# BUTTON.net
KiCad netlist of a schematic drawn in Altium Designer
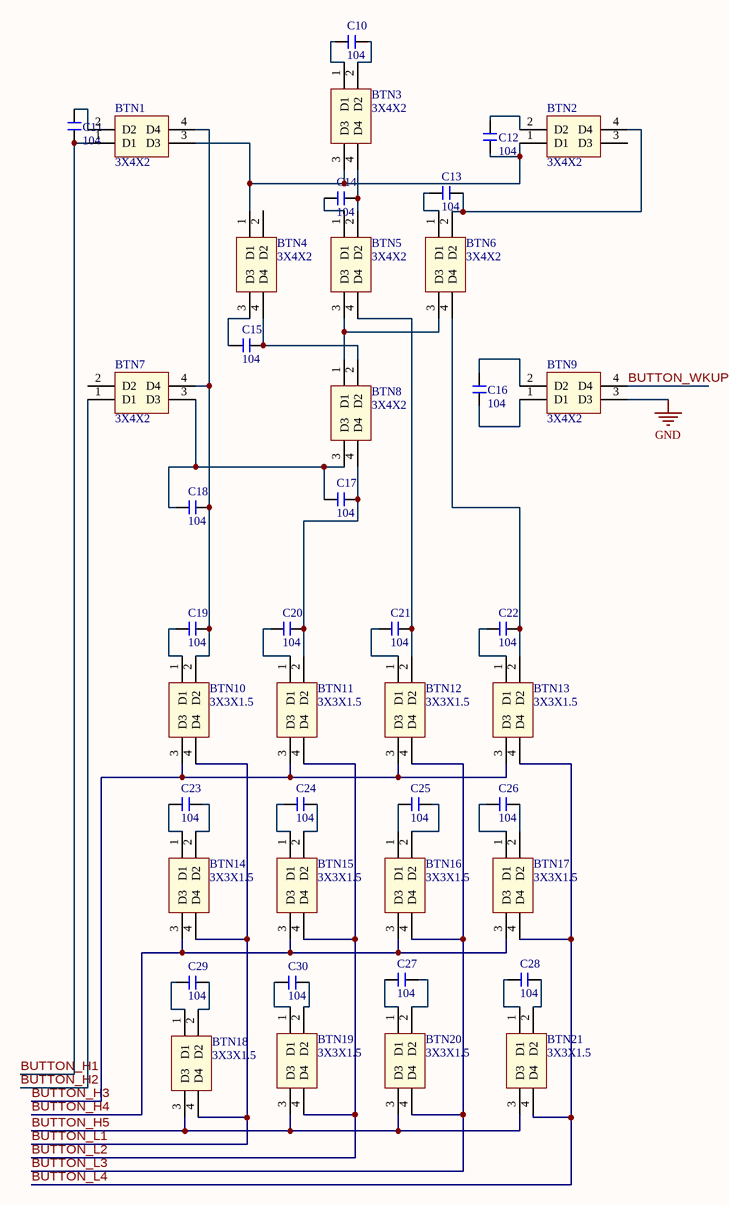
[diagram p0: BUTTON.SchDoc]

(export (version "E")
  (design (tool "Eeschema 10.0.6"))
  (components
    (comp (ref "BTN1") (value "3X4X2") (footprint "3X4X2按钮") (libsource (lib "") (part "3X4X2_1")))
    (comp (ref "BTN2") (value "3X4X2") (footprint "3X4X2按钮") (libsource (lib "") (part "3X4X2_1")))
    (comp (ref "BTN3") (value "3X4X2") (footprint "3X4X2按钮") (libsource (lib "STM32_Phone") (part "3X4X2")))
    (comp (ref "BTN4") (value "3X4X2") (footprint "3X4X2按钮") (libsource (lib "STM32_Phone") (part "3X4X2")))
    (comp (ref "BTN5") (value "3X4X2") (footprint "3X4X2按钮") (libsource (lib "STM32_Phone") (part "3X4X2")))
    (comp (ref "BTN6") (value "3X4X2") (footprint "3X4X2按钮") (libsource (lib "STM32_Phone") (part "3X4X2")))
    (comp (ref "BTN7") (value "3X4X2") (footprint "3X4X2按钮") (libsource (lib "") (part "3X4X2_1")))
    (comp (ref "BTN8") (value "3X4X2") (footprint "3X4X2按钮") (libsource (lib "STM32_Phone") (part "3X4X2")))
    (comp (ref "BTN9") (value "3X4X2") (footprint "3X4X2按钮") (libsource (lib "") (part "3X4X2_1")))
    (comp (ref "BTN10")
      (value "3X3X1.5")
      (footprint "3X3X1.5")
      (libsource (lib "STM32_Phone") (part "3X3X1.5"))
    )
    (comp (ref "BTN11")
      (value "3X3X1.5")
      (footprint "3X3X1.5")
      (libsource (lib "STM32_Phone") (part "3X3X1.5"))
    )
    (comp (ref "BTN12")
      (value "3X3X1.5")
      (footprint "3X3X1.5")
      (libsource (lib "STM32_Phone") (part "3X3X1.5"))
    )
    (comp (ref "BTN13")
      (value "3X3X1.5")
      (footprint "3X3X1.5")
      (libsource (lib "STM32_Phone") (part "3X3X1.5"))
    )
    (comp (ref "BTN14")
      (value "3X3X1.5")
      (footprint "3X3X1.5")
      (libsource (lib "STM32_Phone") (part "3X3X1.5"))
    )
    (comp (ref "BTN15")
      (value "3X3X1.5")
      (footprint "3X3X1.5")
      (libsource (lib "STM32_Phone") (part "3X3X1.5"))
    )
    (comp (ref "BTN16")
      (value "3X3X1.5")
      (footprint "3X3X1.5")
      (libsource (lib "STM32_Phone") (part "3X3X1.5"))
    )
    (comp (ref "BTN17")
      (value "3X3X1.5")
      (footprint "3X3X1.5")
      (libsource (lib "STM32_Phone") (part "3X3X1.5"))
    )
    (comp (ref "BTN18")
      (value "3X3X1.5")
      (footprint "3X3X1.5")
      (libsource (lib "STM32_Phone") (part "3X3X1.5"))
    )
    (comp (ref "BTN19")
      (value "3X3X1.5")
      (footprint "3X3X1.5")
      (libsource (lib "STM32_Phone") (part "3X3X1.5"))
    )
    (comp (ref "BTN20")
      (value "3X3X1.5")
      (footprint "3X3X1.5")
      (libsource (lib "STM32_Phone") (part "3X3X1.5"))
    )
    (comp (ref "BTN21")
      (value "3X3X1.5")
      (footprint "3X3X1.5")
      (libsource (lib "STM32_Phone") (part "3X3X1.5"))
    )
    (comp (ref "C10")
      (value "104")
      (footprint "C 0805_L")
      (description "无极性贴片电容")
      (fields (field (name "版权归属") "源创客"))
      (libsource (lib "STM32_Phone_1") (part "C"))
    )
    (comp (ref "C11")
      (value "104")
      (footprint "C 0805_L")
      (description "无极性贴片电容")
      (fields (field (name "版权归属") "源创客"))
      (libsource (lib "STM32_Phone_1") (part "C"))
    )
    (comp (ref "C12")
      (value "104")
      (footprint "C 0805_L")
      (description "无极性贴片电容")
      (fields (field (name "版权归属") "源创客"))
      (libsource (lib "STM32_Phone_1") (part "C"))
    )
    (comp (ref "C13")
      (value "104")
      (footprint "C 0805_L")
      (description "无极性贴片电容")
      (fields (field (name "版权归属") "源创客"))
      (libsource (lib "STM32_Phone_1") (part "C"))
    )
    (comp (ref "C14")
      (value "104")
      (footprint "C 0805_L")
      (description "无极性贴片电容")
      (fields (field (name "版权归属") "源创客"))
      (libsource (lib "STM32_Phone_1") (part "C"))
    )
    (comp (ref "C15")
      (value "104")
      (footprint "C 0805_L")
      (description "无极性贴片电容")
      (fields (field (name "版权归属") "源创客"))
      (libsource (lib "STM32_Phone_1") (part "C"))
    )
    (comp (ref "C16")
      (value "104")
      (footprint "C 0805_L")
      (description "无极性贴片电容")
      (fields (field (name "版权归属") "源创客"))
      (libsource (lib "STM32_Phone_1") (part "C"))
    )
    (comp (ref "C17")
      (value "104")
      (footprint "C 0805_L")
      (description "无极性贴片电容")
      (fields (field (name "版权归属") "源创客"))
      (libsource (lib "STM32_Phone_1") (part "C"))
    )
    (comp (ref "C18")
      (value "104")
      (footprint "C 0805_L")
      (description "无极性贴片电容")
      (fields (field (name "版权归属") "源创客"))
      (libsource (lib "STM32_Phone_1") (part "C"))
    )
    (comp (ref "C19")
      (value "104")
      (footprint "C 0805_L")
      (description "无极性贴片电容")
      (fields (field (name "版权归属") "源创客"))
      (libsource (lib "STM32_Phone_1") (part "C"))
    )
    (comp (ref "C20")
      (value "104")
      (footprint "C 0805_L")
      (description "无极性贴片电容")
      (fields (field (name "版权归属") "源创客"))
      (libsource (lib "STM32_Phone_1") (part "C"))
    )
    (comp (ref "C21")
      (value "104")
      (footprint "C 0805_L")
      (description "无极性贴片电容")
      (fields (field (name "版权归属") "源创客"))
      (libsource (lib "STM32_Phone_1") (part "C"))
    )
    (comp (ref "C22")
      (value "104")
      (footprint "C 0805_L")
      (description "无极性贴片电容")
      (fields (field (name "版权归属") "源创客"))
      (libsource (lib "STM32_Phone_1") (part "C"))
    )
    (comp (ref "C23")
      (value "104")
      (footprint "C 0805_L")
      (description "无极性贴片电容")
      (fields (field (name "版权归属") "源创客"))
      (libsource (lib "STM32_Phone_1") (part "C"))
    )
    (comp (ref "C24")
      (value "104")
      (footprint "C 0805_L")
      (description "无极性贴片电容")
      (fields (field (name "版权归属") "源创客"))
      (libsource (lib "STM32_Phone_1") (part "C"))
    )
    (comp (ref "C25")
      (value "104")
      (footprint "C 0805_L")
      (description "无极性贴片电容")
      (fields (field (name "版权归属") "源创客"))
      (libsource (lib "STM32_Phone_1") (part "C"))
    )
    (comp (ref "C26")
      (value "104")
      (footprint "C 0805_L")
      (description "无极性贴片电容")
      (fields (field (name "版权归属") "源创客"))
      (libsource (lib "STM32_Phone_1") (part "C"))
    )
    (comp (ref "C27")
      (value "104")
      (footprint "C 0805_L")
      (description "无极性贴片电容")
      (fields (field (name "版权归属") "源创客"))
      (libsource (lib "STM32_Phone_1") (part "C"))
    )
    (comp (ref "C28")
      (value "104")
      (footprint "C 0805_L")
      (description "无极性贴片电容")
      (fields (field (name "版权归属") "源创客"))
      (libsource (lib "STM32_Phone_1") (part "C"))
    )
    (comp (ref "C29")
      (value "104")
      (footprint "C 0805_L")
      (description "无极性贴片电容")
      (fields (field (name "版权归属") "源创客"))
      (libsource (lib "STM32_Phone_1") (part "C"))
    )
    (comp (ref "C30")
      (value "104")
      (footprint "C 0805_L")
      (description "无极性贴片电容")
      (fields (field (name "版权归属") "源创客"))
      (libsource (lib "STM32_Phone_1") (part "C"))
    )
  )
  (nets
    (net (code "1") (name "/BUTTON_H1") (class "Default")
      (node (ref "BTN1") (pin "1") (pinfunction "D1_1") (pintype "passive"))
      (node (ref "C11") (pin "1") (pinfunction "1_1") (pintype "passive"))
    )
    (net (code "2") (name "/BUTTON_H2") (class "Default")
      (node (ref "BTN7") (pin "1") (pinfunction "D1_1") (pintype "passive"))
    )
    (net (code "3") (name "/BUTTON_H3") (class "Default")
      (node (ref "BTN10") (pin "3") (pinfunction "D3_3") (pintype "passive"))
      (node (ref "BTN11") (pin "3") (pinfunction "D3_3") (pintype "passive"))
      (node (ref "BTN12") (pin "3") (pinfunction "D3_3") (pintype "passive"))
      (node (ref "BTN13") (pin "3") (pinfunction "D3_3") (pintype "passive"))
    )
    (net (code "4") (name "/BUTTON_H4") (class "Default")
      (node (ref "BTN14") (pin "3") (pinfunction "D3_3") (pintype "passive"))
      (node (ref "BTN15") (pin "3") (pinfunction "D3_3") (pintype "passive"))
      (node (ref "BTN16") (pin "3") (pinfunction "D3_3") (pintype "passive"))
      (node (ref "BTN17") (pin "3") (pinfunction "D3_3") (pintype "passive"))
    )
    (net (code "5") (name "/BUTTON_H5") (class "Default")
      (node (ref "BTN18") (pin "3") (pinfunction "D3_3") (pintype "passive"))
      (node (ref "BTN19") (pin "3") (pinfunction "D3_3") (pintype "passive"))
      (node (ref "BTN20") (pin "3") (pinfunction "D3_3") (pintype "passive"))
      (node (ref "BTN21") (pin "3") (pinfunction "D3_3") (pintype "passive"))
    )
    (net (code "6") (name "/BUTTON_L1") (class "Default")
      (node (ref "BTN10") (pin "4") (pinfunction "D4_4") (pintype "passive"))
      (node (ref "BTN14") (pin "4") (pinfunction "D4_4") (pintype "passive"))
      (node (ref "BTN18") (pin "4") (pinfunction "D4_4") (pintype "passive"))
    )
    (net (code "7") (name "/BUTTON_L2") (class "Default")
      (node (ref "BTN11") (pin "4") (pinfunction "D4_4") (pintype "passive"))
      (node (ref "BTN15") (pin "4") (pinfunction "D4_4") (pintype "passive"))
      (node (ref "BTN19") (pin "4") (pinfunction "D4_4") (pintype "passive"))
    )
    (net (code "8") (name "/BUTTON_L3") (class "Default")
      (node (ref "BTN12") (pin "4") (pinfunction "D4_4") (pintype "passive"))
      (node (ref "BTN16") (pin "4") (pinfunction "D4_4") (pintype "passive"))
      (node (ref "BTN20") (pin "4") (pinfunction "D4_4") (pintype "passive"))
    )
    (net (code "9") (name "/BUTTON_L4") (class "Default")
      (node (ref "BTN13") (pin "4") (pinfunction "D4_4") (pintype "passive"))
      (node (ref "BTN17") (pin "4") (pinfunction "D4_4") (pintype "passive"))
      (node (ref "BTN21") (pin "4") (pinfunction "D4_4") (pintype "passive"))
    )
    (net (code "10") (name "/BUTTON_WKUP") (class "Default")
      (node (ref "BTN9") (pin "4") (pinfunction "D4_4") (pintype "passive"))
    )
    (net (code "11") (name "GND") (class "Default")
      (node (ref "BTN9") (pin "3") (pinfunction "D3_3") (pintype "passive"))
    )
    (net (code "12") (name "Net-(BTN1-D2)") (class "Default")
      (node (ref "BTN1") (pin "2") (pinfunction "D2_2") (pintype "passive"))
      (node (ref "C11") (pin "2") (pinfunction "2_2") (pintype "passive"))
    )
    (net (code "13") (name "Net-(BTN1-D3)") (class "Default")
      (node (ref "BTN1") (pin "3") (pinfunction "D3_3") (pintype "passive"))
      (node (ref "BTN2") (pin "1") (pinfunction "D1_1") (pintype "passive"))
      (node (ref "BTN3") (pin "3") (pinfunction "D3_3") (pintype "passive"))
      (node (ref "BTN4") (pin "1") (pinfunction "D1_1") (pintype "passive"))
      (node (ref "C12") (pin "1") (pinfunction "1_1") (pintype "passive"))
    )
    (net (code "14") (name "Net-(BTN1-D4)") (class "Default")
      (node (ref "BTN1") (pin "4") (pinfunction "D4_4") (pintype "passive"))
      (node (ref "BTN10") (pin "2") (pinfunction "D2_2") (pintype "passive"))
      (node (ref "BTN7") (pin "4") (pinfunction "D4_4") (pintype "passive"))
      (node (ref "C18") (pin "1") (pinfunction "1_1") (pintype "passive"))
      (node (ref "C19") (pin "1") (pinfunction "1_1") (pintype "passive"))
    )
    (net (code "15") (name "Net-(BTN2-D2)") (class "Default")
      (node (ref "BTN2") (pin "2") (pinfunction "D2_2") (pintype "passive"))
      (node (ref "C12") (pin "2") (pinfunction "2_2") (pintype "passive"))
    )
    (net (code "16") (name "Net-(BTN2-D4)") (class "Default")
      (node (ref "BTN2") (pin "4") (pinfunction "D4_4") (pintype "passive"))
      (node (ref "BTN6") (pin "2") (pinfunction "D2_2") (pintype "passive"))
      (node (ref "C13") (pin "2") (pinfunction "2_2") (pintype "passive"))
    )
    (net (code "17") (name "Net-(BTN3-D1)") (class "Default")
      (node (ref "BTN3") (pin "1") (pinfunction "D1_1") (pintype "passive"))
      (node (ref "C10") (pin "1") (pinfunction "1_1") (pintype "passive"))
    )
    (net (code "18") (name "Net-(BTN3-D2)") (class "Default")
      (node (ref "BTN3") (pin "2") (pinfunction "D2_2") (pintype "passive"))
      (node (ref "C10") (pin "2") (pinfunction "2_2") (pintype "passive"))
    )
    (net (code "19") (name "Net-(BTN3-D4)") (class "Default")
      (node (ref "BTN3") (pin "4") (pinfunction "D4_4") (pintype "passive"))
      (node (ref "BTN5") (pin "2") (pinfunction "D2_2") (pintype "passive"))
      (node (ref "C14") (pin "2") (pinfunction "2_2") (pintype "passive"))
    )
    (net (code "20") (name "Net-(BTN4-D3)") (class "Default")
      (node (ref "BTN4") (pin "3") (pinfunction "D3_3") (pintype "passive"))
      (node (ref "C15") (pin "1") (pinfunction "1_1") (pintype "passive"))
    )
    (net (code "21") (name "Net-(BTN4-D4)") (class "Default")
      (node (ref "BTN4") (pin "4") (pinfunction "D4_4") (pintype "passive"))
      (node (ref "BTN8") (pin "2") (pinfunction "D2_2") (pintype "passive"))
      (node (ref "C15") (pin "2") (pinfunction "2_2") (pintype "passive"))
    )
    (net (code "22") (name "Net-(BTN5-D1)") (class "Default")
      (node (ref "BTN5") (pin "1") (pinfunction "D1_1") (pintype "passive"))
      (node (ref "C14") (pin "1") (pinfunction "1_1") (pintype "passive"))
    )
    (net (code "23") (name "Net-(BTN5-D3)") (class "Default")
      (node (ref "BTN5") (pin "3") (pinfunction "D3_3") (pintype "passive"))
      (node (ref "BTN6") (pin "3") (pinfunction "D3_3") (pintype "passive"))
      (node (ref "BTN8") (pin "1") (pinfunction "D1_1") (pintype "passive"))
    )
    (net (code "24") (name "Net-(BTN6-D1)") (class "Default")
      (node (ref "BTN6") (pin "1") (pinfunction "D1_1") (pintype "passive"))
      (node (ref "C13") (pin "1") (pinfunction "1_1") (pintype "passive"))
    )
    (net (code "25") (name "Net-(BTN7-D3)") (class "Default")
      (node (ref "BTN7") (pin "3") (pinfunction "D3_3") (pintype "passive"))
      (node (ref "BTN8") (pin "3") (pinfunction "D3_3") (pintype "passive"))
      (node (ref "C17") (pin "1") (pinfunction "1_1") (pintype "passive"))
      (node (ref "C18") (pin "2") (pinfunction "2_2") (pintype "passive"))
    )
    (net (code "26") (name "Net-(BTN9-D1)") (class "Default")
      (node (ref "BTN9") (pin "1") (pinfunction "D1_1") (pintype "passive"))
      (node (ref "C16") (pin "1") (pinfunction "1_1") (pintype "passive"))
    )
    (net (code "27") (name "Net-(BTN9-D2)") (class "Default")
      (node (ref "BTN9") (pin "2") (pinfunction "D2_2") (pintype "passive"))
      (node (ref "C16") (pin "2") (pinfunction "2_2") (pintype "passive"))
    )
    (net (code "28") (name "Net-(BTN10-D1)") (class "Default")
      (node (ref "BTN10") (pin "1") (pinfunction "D1_1") (pintype "passive"))
      (node (ref "C19") (pin "2") (pinfunction "2_2") (pintype "passive"))
    )
    (net (code "29") (name "Net-(BTN11-D1)") (class "Default")
      (node (ref "BTN11") (pin "1") (pinfunction "D1_1") (pintype "passive"))
      (node (ref "C20") (pin "2") (pinfunction "2_2") (pintype "passive"))
    )
    (net (code "30") (name "Net-(BTN11-D2)") (class "Default")
      (node (ref "BTN11") (pin "2") (pinfunction "D2_2") (pintype "passive"))
      (node (ref "BTN8") (pin "4") (pinfunction "D4_4") (pintype "passive"))
      (node (ref "C17") (pin "2") (pinfunction "2_2") (pintype "passive"))
      (node (ref "C20") (pin "1") (pinfunction "1_1") (pintype "passive"))
    )
    (net (code "31") (name "Net-(BTN12-D1)") (class "Default")
      (node (ref "BTN12") (pin "1") (pinfunction "D1_1") (pintype "passive"))
      (node (ref "C21") (pin "2") (pinfunction "2_2") (pintype "passive"))
    )
    (net (code "32") (name "Net-(BTN12-D2)") (class "Default")
      (node (ref "BTN12") (pin "2") (pinfunction "D2_2") (pintype "passive"))
      (node (ref "BTN5") (pin "4") (pinfunction "D4_4") (pintype "passive"))
      (node (ref "C21") (pin "1") (pinfunction "1_1") (pintype "passive"))
    )
    (net (code "33") (name "Net-(BTN13-D1)") (class "Default")
      (node (ref "BTN13") (pin "1") (pinfunction "D1_1") (pintype "passive"))
      (node (ref "C22") (pin "2") (pinfunction "2_2") (pintype "passive"))
    )
    (net (code "34") (name "Net-(BTN13-D2)") (class "Default")
      (node (ref "BTN13") (pin "2") (pinfunction "D2_2") (pintype "passive"))
      (node (ref "BTN6") (pin "4") (pinfunction "D4_4") (pintype "passive"))
      (node (ref "C22") (pin "1") (pinfunction "1_1") (pintype "passive"))
    )
    (net (code "35") (name "Net-(BTN14-D1)") (class "Default")
      (node (ref "BTN14") (pin "1") (pinfunction "D1_1") (pintype "passive"))
      (node (ref "C23") (pin "2") (pinfunction "2_2") (pintype "passive"))
    )
    (net (code "36") (name "Net-(BTN14-D2)") (class "Default")
      (node (ref "BTN14") (pin "2") (pinfunction "D2_2") (pintype "passive"))
      (node (ref "C23") (pin "1") (pinfunction "1_1") (pintype "passive"))
    )
    (net (code "37") (name "Net-(BTN15-D1)") (class "Default")
      (node (ref "BTN15") (pin "1") (pinfunction "D1_1") (pintype "passive"))
      (node (ref "C24") (pin "2") (pinfunction "2_2") (pintype "passive"))
    )
    (net (code "38") (name "Net-(BTN15-D2)") (class "Default")
      (node (ref "BTN15") (pin "2") (pinfunction "D2_2") (pintype "passive"))
      (node (ref "C24") (pin "1") (pinfunction "1_1") (pintype "passive"))
    )
    (net (code "39") (name "Net-(BTN16-D1)") (class "Default")
      (node (ref "BTN16") (pin "1") (pinfunction "D1_1") (pintype "passive"))
      (node (ref "C25") (pin "1") (pinfunction "1_1") (pintype "passive"))
    )
    (net (code "40") (name "Net-(BTN16-D2)") (class "Default")
      (node (ref "BTN16") (pin "2") (pinfunction "D2_2") (pintype "passive"))
      (node (ref "C25") (pin "2") (pinfunction "2_2") (pintype "passive"))
    )
    (net (code "41") (name "Net-(BTN17-D1)") (class "Default")
      (node (ref "BTN17") (pin "1") (pinfunction "D1_1") (pintype "passive"))
      (node (ref "C26") (pin "2") (pinfunction "2_2") (pintype "passive"))
    )
    (net (code "42") (name "Net-(BTN17-D2)") (class "Default")
      (node (ref "BTN17") (pin "2") (pinfunction "D2_2") (pintype "passive"))
      (node (ref "C26") (pin "1") (pinfunction "1_1") (pintype "passive"))
    )
    (net (code "43") (name "Net-(BTN18-D1)") (class "Default")
      (node (ref "BTN18") (pin "1") (pinfunction "D1_1") (pintype "passive"))
      (node (ref "C29") (pin "2") (pinfunction "2_2") (pintype "passive"))
    )
    (net (code "44") (name "Net-(BTN18-D2)") (class "Default")
      (node (ref "BTN18") (pin "2") (pinfunction "D2_2") (pintype "passive"))
      (node (ref "C29") (pin "1") (pinfunction "1_1") (pintype "passive"))
    )
    (net (code "45") (name "Net-(BTN19-D1)") (class "Default")
      (node (ref "BTN19") (pin "1") (pinfunction "D1_1") (pintype "passive"))
      (node (ref "C30") (pin "2") (pinfunction "2_2") (pintype "passive"))
    )
    (net (code "46") (name "Net-(BTN19-D2)") (class "Default")
      (node (ref "BTN19") (pin "2") (pinfunction "D2_2") (pintype "passive"))
      (node (ref "C30") (pin "1") (pinfunction "1_1") (pintype "passive"))
    )
    (net (code "47") (name "Net-(BTN20-D1)") (class "Default")
      (node (ref "BTN20") (pin "1") (pinfunction "D1_1") (pintype "passive"))
      (node (ref "C27") (pin "2") (pinfunction "2_2") (pintype "passive"))
    )
    (net (code "48") (name "Net-(BTN20-D2)") (class "Default")
      (node (ref "BTN20") (pin "2") (pinfunction "D2_2") (pintype "passive"))
      (node (ref "C27") (pin "1") (pinfunction "1_1") (pintype "passive"))
    )
    (net (code "49") (name "Net-(BTN21-D1)") (class "Default")
      (node (ref "BTN21") (pin "1") (pinfunction "D1_1") (pintype "passive"))
      (node (ref "C28") (pin "2") (pinfunction "2_2") (pintype "passive"))
    )
    (net (code "50") (name "Net-(BTN21-D2)") (class "Default")
      (node (ref "BTN21") (pin "2") (pinfunction "D2_2") (pintype "passive"))
      (node (ref "C28") (pin "1") (pinfunction "1_1") (pintype "passive"))
    )
    (net (code "51") (name "unconnected-(BTN2-D3-Pad3)") (class "Default")
      (node (ref "BTN2") (pin "3") (pinfunction "D3_3") (pintype "passive"))
    )
    (net (code "52") (name "unconnected-(BTN4-D2-Pad2)") (class "Default")
      (node (ref "BTN4") (pin "2") (pinfunction "D2_2") (pintype "passive"))
    )
    (net (code "53") (name "unconnected-(BTN7-D2-Pad2)") (class "Default")
      (node (ref "BTN7") (pin "2") (pinfunction "D2_2") (pintype "passive"))
    )
  )
)
